# Sheet6.net
KiCad netlist of a schematic drawn in Altium Designer
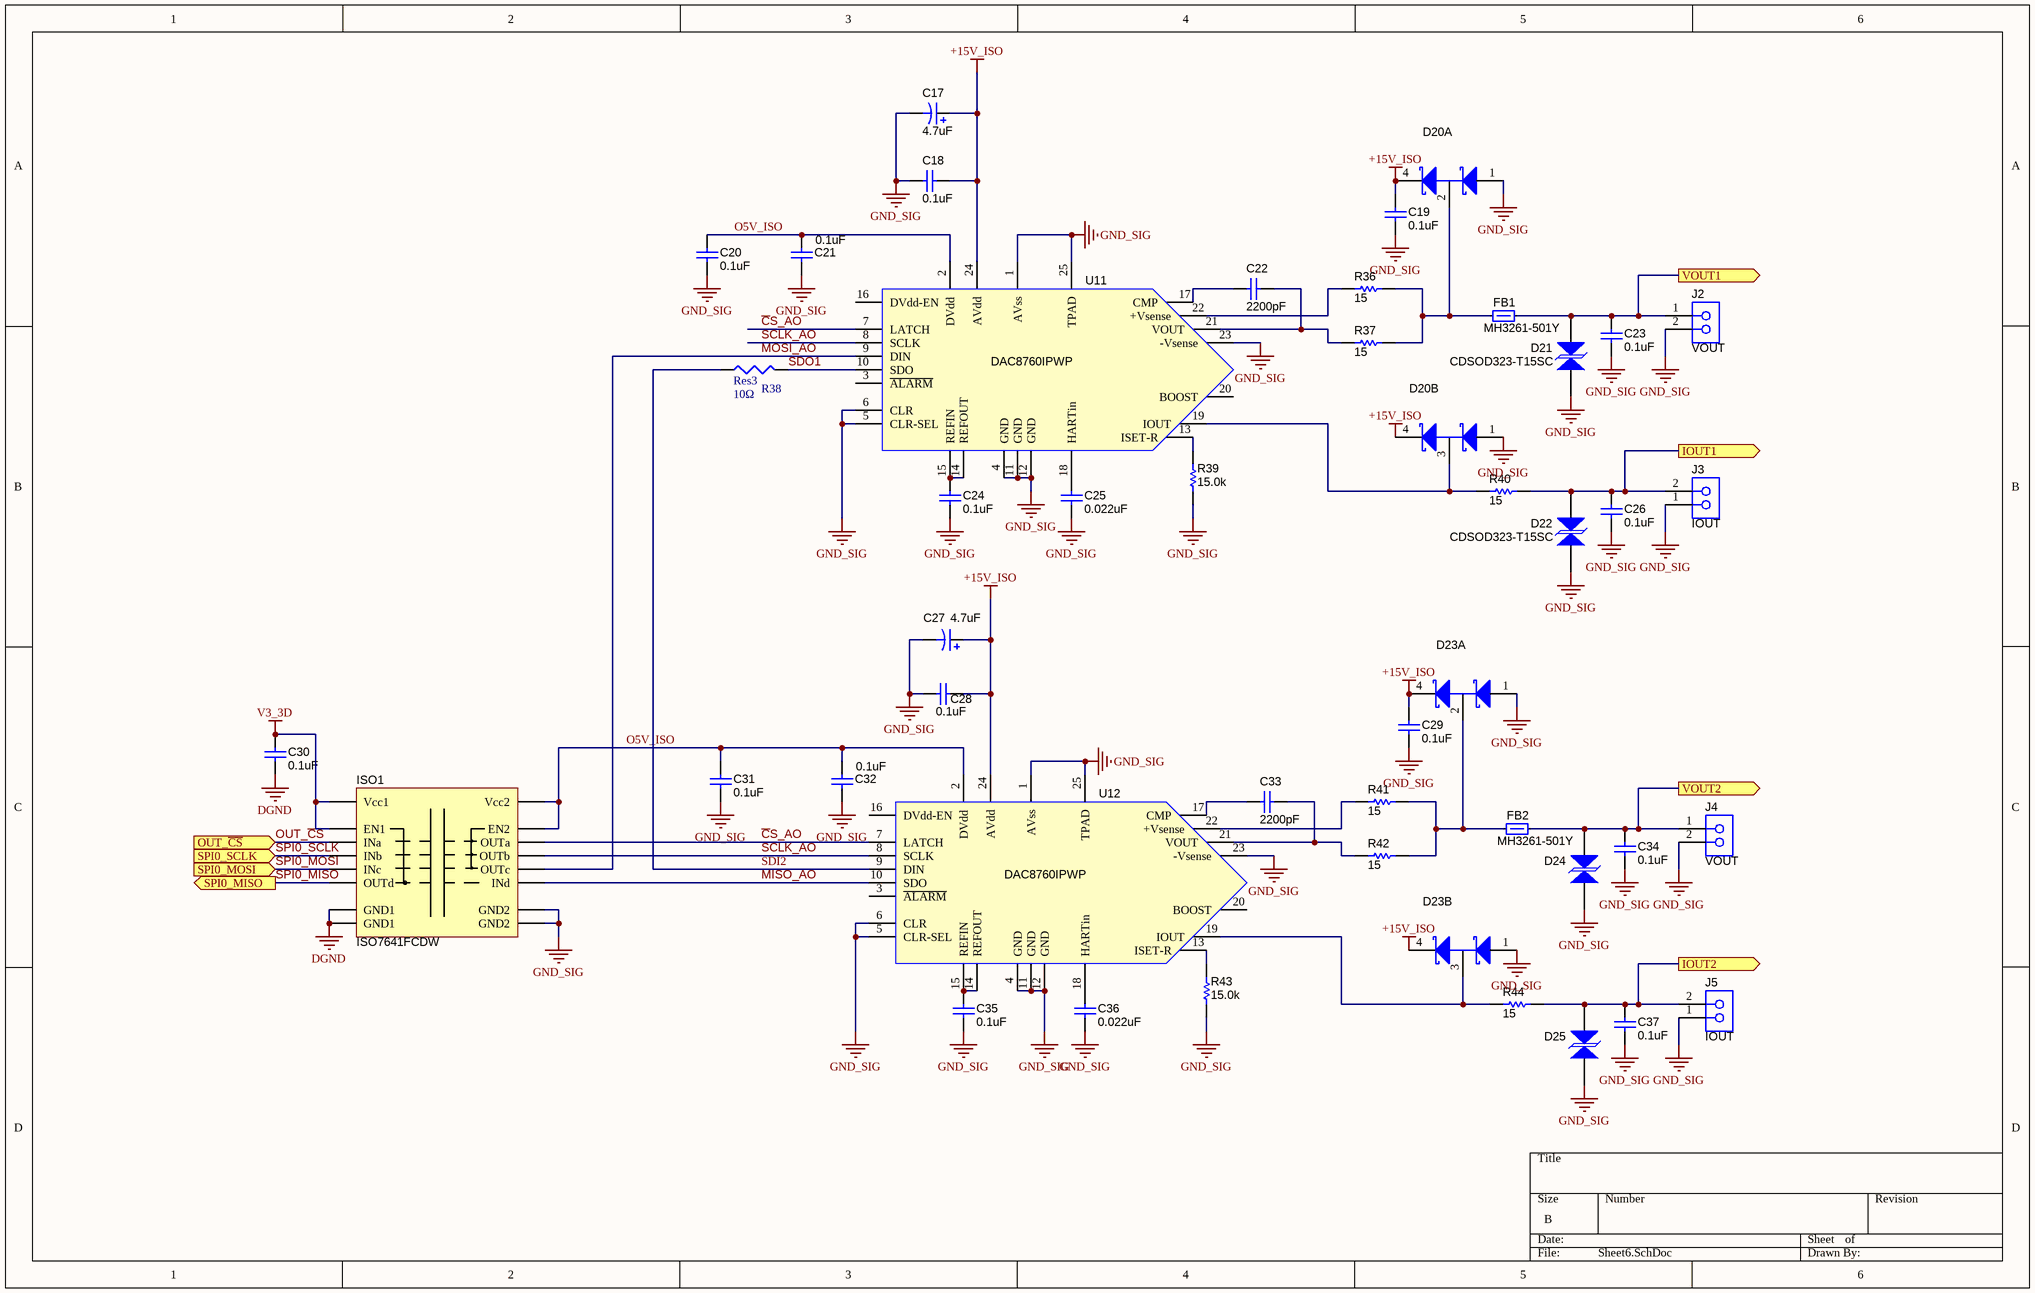
[diagram p0: Sheet6.SchDoc]

(export (version "E")
  (design (tool "Eeschema 10.0.6"))
  (components
    (comp (ref "C17")
      (value "293D475X9035C2TE3")
      (footprint "6032-28")
      (description "CAP, TA, 4.7uF, 35V, +/-10%, 1.9 ohm, SMD")
      (fields
        (field (name "VALUEDISPLAYED") "4.7uF")
        (field (name "MANUFACTURER") "Vishay-Sprague")
        (field (name "PUBLISHER") "Texas Instruments")
      )
      (libsource (lib "Capacitor_Tantalum") (part "293D475X9035C2TE3"))
    )
    (comp (ref "C18")
      (value "GRM188R71H104KA93D")
      (footprint "0805_cap")
      (description "CAP, CERM, 0.1uF, 50V, +/-10%, X7R, 0603")
      (fields
        (field (name "VALUEDISPLAYED") "0.1uF")
        (field (name "MANUFACTURER") "MuRata")
        (field (name "PUBLISHER") "Texas Instruments")
      )
      (libsource (lib "Capacitor_Ceramic") (part "GRM188R71H104KA93D"))
    )
    (comp (ref "C19")
      (value "GRM188R71H104KA93D")
      (footprint "0805_cap")
      (description "CAP, CERM, 0.1uF, 50V, +/-10%, X7R, 0603")
      (fields
        (field (name "VALUEDISPLAYED") "0.1uF")
        (field (name "MANUFACTURER") "MuRata")
        (field (name "PUBLISHER") "Texas Instruments")
      )
      (libsource (lib "Capacitor_Ceramic") (part "GRM188R71H104KA93D"))
    )
    (comp (ref "C20")
      (value "GRM188R71H104KA93D")
      (footprint "0805_cap")
      (description "CAP, CERM, 0.1uF, 50V, +/-10%, X7R, 0603")
      (fields
        (field (name "VALUEDISPLAYED") "0.1uF")
        (field (name "MANUFACTURER") "MuRata")
        (field (name "PUBLISHER") "Texas Instruments")
      )
      (libsource (lib "Capacitor_Ceramic") (part "GRM188R71H104KA93D"))
    )
    (comp (ref "C21")
      (value "GRM188R71H104KA93D")
      (footprint "0805_cap")
      (description "CAP, CERM, 0.1uF, 50V, +/-10%, X7R, 0603")
      (fields
        (field (name "VALUEDISPLAYED") "0.1uF")
        (field (name "MANUFACTURER") "MuRata")
        (field (name "PUBLISHER") "Texas Instruments")
      )
      (libsource (lib "Capacitor_Ceramic") (part "GRM188R71H104KA93D"))
    )
    (comp (ref "C22")
      (value "GRM1885C1H222JA01D")
      (footprint "0805_cap")
      (description "CAP, CERM, 2200pF, 50V, +/-5%, C0G/NP0, 0603")
      (fields
        (field (name "VALUEDISPLAYED") "2200pF")
        (field (name "MANUFACTURER") "MuRata")
        (field (name "PUBLISHER") "Texas Instruments")
      )
      (libsource (lib "Capacitor_Ceramic") (part "GRM1885C1H222JA01D"))
    )
    (comp (ref "C23")
      (value "06035C104KAT2A")
      (footprint "0805_cap")
      (description "CAP, CERM, 0.1uF, 50V, +/-10%, X7R, 0603")
      (fields
        (field (name "VALUEDISPLAYED") "0.1uF")
        (field (name "MANUFACTURER") "AVX")
        (field (name "PUBLISHER") "Texas Instruments")
      )
      (libsource (lib "Capacitor_Ceramic") (part "06035C104KAT2A"))
    )
    (comp (ref "C24")
      (value "06035C104KAT2A")
      (footprint "0805_cap")
      (description "CAP, CERM, 0.1uF, 50V, +/-10%, X7R, 0603")
      (fields
        (field (name "VALUEDISPLAYED") "0.1uF")
        (field (name "MANUFACTURER") "AVX")
        (field (name "PUBLISHER") "Texas Instruments")
      )
      (libsource (lib "Capacitor_Ceramic") (part "06035C104KAT2A"))
    )
    (comp (ref "C25")
      (value "C1608X7R1H223K")
      (footprint "0805_cap")
      (description "CAP, CERM, 0.022uF, 50V, +/-10%, X7R, 0603")
      (fields
        (field (name "VALUEDISPLAYED") "0.022uF")
        (field (name "MANUFACTURER") "TDK")
        (field (name "PUBLISHER") "Texas Instruments")
      )
      (libsource (lib "Capacitor_Ceramic") (part "C1608X7R1H223K"))
    )
    (comp (ref "C26")
      (value "06035C104KAT2A")
      (footprint "0805_cap")
      (description "CAP, CERM, 0.1uF, 50V, +/-10%, X7R, 0603")
      (fields
        (field (name "VALUEDISPLAYED") "0.1uF")
        (field (name "MANUFACTURER") "AVX")
        (field (name "PUBLISHER") "Texas Instruments")
      )
      (libsource (lib "Capacitor_Ceramic") (part "06035C104KAT2A"))
    )
    (comp (ref "C27")
      (value "293D475X9035C2TE3")
      (footprint "6032-28")
      (description "CAP, TA, 4.7uF, 35V, +/-10%, 1.9 ohm, SMD")
      (fields
        (field (name "VALUEDISPLAYED") "4.7uF")
        (field (name "MANUFACTURER") "Vishay-Sprague")
        (field (name "PUBLISHER") "Texas Instruments")
      )
      (libsource (lib "Capacitor_Tantalum") (part "293D475X9035C2TE3"))
    )
    (comp (ref "C28")
      (value "GRM188R71H104KA93D")
      (footprint "0805_cap")
      (description "CAP, CERM, 0.1uF, 50V, +/-10%, X7R, 0603")
      (fields
        (field (name "VALUEDISPLAYED") "0.1uF")
        (field (name "MANUFACTURER") "MuRata")
        (field (name "PUBLISHER") "Texas Instruments")
      )
      (libsource (lib "Capacitor_Ceramic") (part "GRM188R71H104KA93D"))
    )
    (comp (ref "C29")
      (value "GRM188R71H104KA93D")
      (footprint "0805_cap")
      (description "CAP, CERM, 0.1uF, 50V, +/-10%, X7R, 0603")
      (fields
        (field (name "VALUEDISPLAYED") "0.1uF")
        (field (name "MANUFACTURER") "MuRata")
        (field (name "PUBLISHER") "Texas Instruments")
      )
      (libsource (lib "Capacitor_Ceramic") (part "GRM188R71H104KA93D"))
    )
    (comp (ref "C30")
      (value "GRM188R71H104KA93D")
      (footprint "0805_cap")
      (description "CAP, CERM, 0.1uF, 50V, +/-10%, X7R, 0603")
      (fields
        (field (name "VALUEDISPLAYED") "0.1uF")
        (field (name "MANUFACTURER") "MuRata")
        (field (name "PUBLISHER") "Texas Instruments")
      )
      (libsource (lib "Capacitor_Ceramic") (part "GRM188R71H104KA93D"))
    )
    (comp (ref "C31")
      (value "GRM188R71H104KA93D")
      (footprint "0805_cap")
      (description "CAP, CERM, 0.1uF, 50V, +/-10%, X7R, 0603")
      (fields
        (field (name "VALUEDISPLAYED") "0.1uF")
        (field (name "MANUFACTURER") "MuRata")
        (field (name "PUBLISHER") "Texas Instruments")
      )
      (libsource (lib "Capacitor_Ceramic") (part "GRM188R71H104KA93D"))
    )
    (comp (ref "C32")
      (value "GRM188R71H104KA93D")
      (footprint "0805_cap")
      (description "CAP, CERM, 0.1uF, 50V, +/-10%, X7R, 0603")
      (fields
        (field (name "VALUEDISPLAYED") "0.1uF")
        (field (name "MANUFACTURER") "MuRata")
        (field (name "PUBLISHER") "Texas Instruments")
      )
      (libsource (lib "Capacitor_Ceramic") (part "GRM188R71H104KA93D"))
    )
    (comp (ref "C33")
      (value "GRM1885C1H222JA01D")
      (footprint "0805_cap")
      (description "CAP, CERM, 2200pF, 50V, +/-5%, C0G/NP0, 0603")
      (fields
        (field (name "VALUEDISPLAYED") "2200pF")
        (field (name "MANUFACTURER") "MuRata")
        (field (name "PUBLISHER") "Texas Instruments")
      )
      (libsource (lib "Capacitor_Ceramic") (part "GRM1885C1H222JA01D"))
    )
    (comp (ref "C34")
      (value "06035C104KAT2A")
      (footprint "0805_cap")
      (description "CAP, CERM, 0.1uF, 50V, +/-10%, X7R, 0603")
      (fields
        (field (name "VALUEDISPLAYED") "0.1uF")
        (field (name "MANUFACTURER") "AVX")
        (field (name "PUBLISHER") "Texas Instruments")
      )
      (libsource (lib "Capacitor_Ceramic") (part "06035C104KAT2A"))
    )
    (comp (ref "C35")
      (value "06035C104KAT2A")
      (footprint "0805_cap")
      (description "CAP, CERM, 0.1uF, 50V, +/-10%, X7R, 0603")
      (fields
        (field (name "VALUEDISPLAYED") "0.1uF")
        (field (name "MANUFACTURER") "AVX")
        (field (name "PUBLISHER") "Texas Instruments")
      )
      (libsource (lib "Capacitor_Ceramic") (part "06035C104KAT2A"))
    )
    (comp (ref "C36")
      (value "C1608X7R1H223K")
      (footprint "0805_cap")
      (description "CAP, CERM, 0.022uF, 50V, +/-10%, X7R, 0603")
      (fields
        (field (name "VALUEDISPLAYED") "0.022uF")
        (field (name "MANUFACTURER") "TDK")
        (field (name "PUBLISHER") "Texas Instruments")
      )
      (libsource (lib "Capacitor_Ceramic") (part "C1608X7R1H223K"))
    )
    (comp (ref "C37")
      (value "06035C104KAT2A")
      (footprint "0805_cap")
      (description "CAP, CERM, 0.1uF, 50V, +/-10%, X7R, 0603")
      (fields
        (field (name "VALUEDISPLAYED") "0.1uF")
        (field (name "MANUFACTURER") "AVX")
        (field (name "PUBLISHER") "Texas Instruments")
      )
      (libsource (lib "Capacitor_Ceramic") (part "06035C104KAT2A"))
    )
    (comp (ref "D20")
      (value "~")
      (footprint "SOT-143")
      (description "IC TVS ARRAY 2-LINE 70V SOT-143")
      (fields
        (field (name "MANUFACTURER") "Bourns")
        (field (name "PARTNUMBER") "CD143A-SR70")
        (field (name "SYMBOLCREATOR") "Use LDAP id")
      )
      (libsource (lib "DAC8760-Symbols") (part "CD143A-SR70"))
    )
    (comp (ref "D21")
      (value "CDSOD323-T15SC")
      (footprint "sod-323")
      (description "DIODE TVS ARRAY 15V SOD323")
      (fields (field (name "MANUFACTURER") "Bourns") (field (name "SYMBOLCREATOR") "Use LDAP id"))
      (libsource (lib "DAC8760-Symbols") (part "SMAJ15CA"))
    )
    (comp (ref "D22")
      (value "CDSOD323-T15SC")
      (footprint "sod-323")
      (description "DIODE TVS ARRAY 15V SOD323")
      (fields (field (name "MANUFACTURER") "Bourns") (field (name "SYMBOLCREATOR") "Use LDAP id"))
      (libsource (lib "DAC8760-Symbols") (part "SMAJ15CA"))
    )
    (comp (ref "D23")
      (value "~")
      (footprint "SOT-143")
      (description "IC TVS ARRAY 2-LINE 70V SOT-143")
      (fields
        (field (name "MANUFACTURER") "Bourns")
        (field (name "PARTNUMBER") "CD143A-SR70")
        (field (name "SYMBOLCREATOR") "Use LDAP id")
      )
      (libsource (lib "DAC8760-Symbols") (part "CD143A-SR70"))
    )
    (comp (ref "D24")
      (value "~")
      (footprint "sod-323")
      (description "DIODE TVS ARRAY 15V SOD323")
      (fields
        (field (name "MANUFACTURER") "Bourns")
        (field (name "PARTNUMBER") "CDSOD323-T15SC")
        (field (name "SYMBOLCREATOR") "Use LDAP id")
      )
      (libsource (lib "DAC8760-Symbols") (part "SMAJ15CA"))
    )
    (comp (ref "D25")
      (value "~")
      (footprint "sod-323")
      (description "DIODE TVS ARRAY 15V SOD323")
      (fields
        (field (name "MANUFACTURER") "Bourns")
        (field (name "PARTNUMBER") "CDSOD323-T15SC")
        (field (name "SYMBOLCREATOR") "Use LDAP id")
      )
      (libsource (lib "DAC8760-Symbols") (part "SMAJ15CA"))
    )
    (comp (ref "FB1")
      (value "MH3261-501Y")
      (footprint "1210")
      (description "BEAD FERRITE 500 OHM 3.0A 3216")
      (fields (field (name "MANUFACTURER") "Bourns Inc.") (field (name "PUBLISHER") "Texas Instruments"))
      (libsource (lib "MiscParts") (part "Ferrite_Bead"))
    )
    (comp (ref "FB2")
      (value "MH3261-501Y")
      (footprint "1210")
      (description "BEAD FERRITE 500 OHM 3.0A 3216")
      (fields (field (name "MANUFACTURER") "Bourns Inc.") (field (name "PUBLISHER") "Texas Instruments"))
      (libsource (lib "MiscParts") (part "Ferrite_Bead"))
    )
    (comp (ref "ISO1")
      (value "ISO7641FCDW")
      (footprint "M16B_N")
      (description "ISOLATOR DGTL 25MBPS 4CH 16SOIC")
      (fields
        (field (name "MANUFACTURER") "Texas Instruments Inc")
        (field (name "SYMBOLCREATOR") "Use LDAP id")
      )
      (libsource (lib "DAC8760-Symbols") (part "ISO7241"))
    )
    (comp (ref "J2")
      (value "VOUT")
      (footprint "ED555/2DS")
      (description "TERMINAL BLOCK 3.5MM 2POS PCB")
      (fields
        (field (name "PARTNUMBER") "ED555/2DS")
        (field (name "MANUFACTURER") "On Shore Technology Inc")
        (field (name "PUBLISHER") "Texas Instruments")
      )
      (libsource (lib "") (part "1727010_1"))
    )
    (comp (ref "J3")
      (value "IOUT")
      (footprint "ED555/2DS")
      (description "TERMINAL BLOCK 3.5MM 2POS PCB")
      (fields
        (field (name "PARTNUMBER") "ED555/2DS")
        (field (name "MANUFACTURER") "On Shore Technology Inc")
        (field (name "PUBLISHER") "Texas Instruments")
      )
      (libsource (lib "Connectors") (part "1727010"))
    )
    (comp (ref "J4")
      (value "VOUT")
      (footprint "ED555/2DS")
      (description "TERMINAL BLOCK 3.5MM 2POS PCB")
      (fields
        (field (name "PARTNUMBER") "ED555/2DS")
        (field (name "MANUFACTURER") "On Shore Technology Inc")
        (field (name "PUBLISHER") "Texas Instruments")
      )
      (libsource (lib "") (part "1727010_1"))
    )
    (comp (ref "J5")
      (value "IOUT")
      (footprint "ED555/2DS")
      (description "TERMINAL BLOCK 3.5MM 2POS PCB")
      (fields
        (field (name "PARTNUMBER") "ED555/2DS")
        (field (name "MANUFACTURER") "On Shore Technology Inc")
        (field (name "PUBLISHER") "Texas Instruments")
      )
      (libsource (lib "Connectors") (part "1727010"))
    )
    (comp (ref "R36")
      (value "15")
      (footprint "0805")
      (description "RES, 15 ohm, 5%, 0.1W, 0603")
      (fields
        (field (name "PARTNUMBER") "CRCW060315R0JNEA")
        (field (name "MANUFACTURER") "Vishay-Dale")
        (field (name "PUBLISHER") "Texas Instruments")
      )
      (libsource (lib "Resistor_0603") (part "CRCW060315R0JNEA"))
    )
    (comp (ref "R37")
      (value "15")
      (footprint "0805")
      (description "RES, 15 ohm, 5%, 0.1W, 0603")
      (fields
        (field (name "PARTNUMBER") "CRCW060315R0JNEA")
        (field (name "MANUFACTURER") "Vishay-Dale")
        (field (name "PUBLISHER") "Texas Instruments")
      )
      (libsource (lib "Resistor_0603") (part "CRCW060315R0JNEA"))
    )
    (comp (ref "R38")
      (value "Res3")
      (footprint "0805")
      (description "Resistor")
      (fields (field (name "ALTIUM_VALUE") "10Ω") (field (name "PUBLISHER") "Altium Limited"))
      (libsource (lib "Miscellaneous Devices") (part "Res3"))
    )
    (comp (ref "R39")
      (value "15.0k")
      (footprint "0805")
      (description "RES, 15.0k ohm, 0.1%, 0.1W, 0603")
      (fields
        (field (name "PARTNUMBER") "RT0603BRD0715KL")
        (field (name "MANUFACTURER") "Yageo America")
        (field (name "PUBLISHER") "Texas Instruments")
      )
      (libsource (lib "Resistor_0603") (part "RT0603BRD0715KL"))
    )
    (comp (ref "R40")
      (value "15")
      (footprint "1210")
      (description "RES 15 OHM 1W 5% 2512")
      (fields
        (field (name "PARTNUMBER") "RPC2512JT15R0")
        (field (name "MANUFACTURER") "Stackpole Electronics")
      )
      (libsource (lib "Resistor_OtherSMT") (part "CRA2512-FZ-R080ELF"))
    )
    (comp (ref "R41")
      (value "15")
      (footprint "0805")
      (description "RES, 15 ohm, 5%, 0.1W, 0603")
      (fields
        (field (name "PARTNUMBER") "CRCW060315R0JNEA")
        (field (name "MANUFACTURER") "Vishay-Dale")
        (field (name "PUBLISHER") "Texas Instruments")
      )
      (libsource (lib "Resistor_0603") (part "CRCW060315R0JNEA"))
    )
    (comp (ref "R42")
      (value "15")
      (footprint "0805")
      (description "RES, 15 ohm, 5%, 0.1W, 0603")
      (fields
        (field (name "PARTNUMBER") "CRCW060315R0JNEA")
        (field (name "MANUFACTURER") "Vishay-Dale")
        (field (name "PUBLISHER") "Texas Instruments")
      )
      (libsource (lib "Resistor_0603") (part "CRCW060315R0JNEA"))
    )
    (comp (ref "R43")
      (value "15.0k")
      (footprint "0805")
      (description "RES, 15.0k ohm, 0.1%, 0.1W, 0603")
      (fields
        (field (name "PARTNUMBER") "RT0603BRD0715KL")
        (field (name "MANUFACTURER") "Yageo America")
        (field (name "PUBLISHER") "Texas Instruments")
      )
      (libsource (lib "Resistor_0603") (part "RT0603BRD0715KL"))
    )
    (comp (ref "R44")
      (value "15")
      (footprint "1210")
      (description "RES 15 OHM 1W 5% 2512")
      (fields
        (field (name "PARTNUMBER") "RPC2512JT15R0")
        (field (name "MANUFACTURER") "Stackpole Electronics")
      )
      (libsource (lib "Resistor_OtherSMT") (part "CRA2512-FZ-R080ELF"))
    )
    (comp (ref "U11")
      (value "DAC8760IPWP")
      (footprint "PWP24-DIE84X166")
      (description "1-Channel, 16-Bit, Programmable Current/Voltage Output DAC for 4-20mA Current Loop Applications")
      (fields
        (field (name "MANUFACTURER") "Texas Instruments")
        (field (name "SYMBOLCREATOR") "x0120606")
        (field (name "PUBLISHER") "Texas Instruments")
      )
      (libsource (lib "dolphi_ecs") (part "DAC8760IPWP_1"))
    )
    (comp (ref "U12")
      (value "DAC8760IPWP")
      (footprint "PWP24-DIE84X166")
      (description "1-Channel, 16-Bit, Programmable Current/Voltage Output DAC for 4-20mA Current Loop Applications")
      (fields
        (field (name "MANUFACTURER") "Texas Instruments")
        (field (name "SYMBOLCREATOR") "x0120606")
        (field (name "PUBLISHER") "Texas Instruments")
      )
      (libsource (lib "dolphi_ecs") (part "DAC8760IPWP_1"))
    )
  )
  (nets
    (net (code "1") (name "+15V_ISO") (class "Default")
      (node (ref "C17") (pin "1") (pinfunction "+_1") (pintype "passive"))
      (node (ref "C18") (pin "1") (pinfunction "1_1") (pintype "passive"))
      (node (ref "C19") (pin "1") (pinfunction "1_1") (pintype "passive"))
      (node (ref "C27") (pin "1") (pinfunction "+_1") (pintype "passive"))
      (node (ref "C28") (pin "1") (pinfunction "1_1") (pintype "passive"))
      (node (ref "C29") (pin "1") (pinfunction "1_1") (pintype "passive"))
      (node (ref "D20") (pin "4") (pinfunction "4_4") (pintype "passive"))
      (node (ref "D23") (pin "4") (pinfunction "4_4") (pintype "passive"))
      (node (ref "U11") (pin "24") (pinfunction "AVdd_24") (pintype "passive"))
      (node (ref "U12") (pin "24") (pinfunction "AVdd_24") (pintype "passive"))
    )
    (net (code "2") (name "/IOUT1") (class "Default")
      (node (ref "C26") (pin "1") (pinfunction "1_1") (pintype "passive"))
      (node (ref "D22") (pin "1") (pinfunction "1_1") (pintype "passive"))
      (node (ref "J3") (pin "2") (pinfunction "2_2") (pintype "passive"))
      (node (ref "R40") (pin "2") (pinfunction "2_2") (pintype "passive"))
    )
    (net (code "3") (name "/IOUT2") (class "Default")
      (node (ref "C37") (pin "1") (pinfunction "1_1") (pintype "passive"))
      (node (ref "D25") (pin "1") (pinfunction "1_1") (pintype "passive"))
      (node (ref "J5") (pin "2") (pinfunction "2_2") (pintype "passive"))
      (node (ref "R44") (pin "2") (pinfunction "2_2") (pintype "passive"))
    )
    (net (code "4") (name "/MISO_AO") (class "Default")
      (node (ref "ISO1") (pin "11") (pinfunction "INd_11") (pintype "passive"))
      (node (ref "U12") (pin "10") (pinfunction "SDO_10") (pintype "passive"))
    )
    (net (code "5") (name "/MOSI_AO") (class "Default")
      (node (ref "ISO1") (pin "12") (pinfunction "OUTc_12") (pintype "passive"))
      (node (ref "U11") (pin "9") (pinfunction "DIN_9") (pintype "passive"))
    )
    (net (code "6") (name "/O5V_ISO") (class "Default")
      (node (ref "C20") (pin "1") (pinfunction "1_1") (pintype "passive"))
      (node (ref "C21") (pin "1") (pinfunction "1_1") (pintype "passive"))
      (node (ref "C31") (pin "1") (pinfunction "1_1") (pintype "passive"))
      (node (ref "C32") (pin "1") (pinfunction "1_1") (pintype "passive"))
      (node (ref "ISO1") (pin "10") (pinfunction "EN2_10") (pintype "passive"))
      (node (ref "ISO1") (pin "16") (pinfunction "Vcc2_16") (pintype "passive"))
      (node (ref "U11") (pin "2") (pinfunction "DVdd_2") (pintype "passive"))
      (node (ref "U12") (pin "2") (pinfunction "DVdd_2") (pintype "passive"))
    )
    (net (code "7") (name "/OUT_~{CS}") (class "Default")
      (node (ref "ISO1") (pin "3") (pinfunction "INa_3") (pintype "passive"))
    )
    (net (code "8") (name "/SCLK_AO") (class "Default")
      (node (ref "ISO1") (pin "13") (pinfunction "OUTb_13") (pintype "passive"))
      (node (ref "U11") (pin "8") (pinfunction "SCLK_8") (pintype "passive"))
      (node (ref "U12") (pin "8") (pinfunction "SCLK_8") (pintype "passive"))
    )
    (net (code "9") (name "/SDI2") (class "Default")
      (node (ref "R38") (pin "1") (pinfunction "1_1") (pintype "passive"))
      (node (ref "U12") (pin "9") (pinfunction "DIN_9") (pintype "passive"))
    )
    (net (code "10") (name "/SDO1") (class "Default")
      (node (ref "R38") (pin "2") (pinfunction "2_2") (pintype "passive"))
      (node (ref "U11") (pin "10") (pinfunction "SDO_10") (pintype "passive"))
    )
    (net (code "11") (name "/SPI0_MISO") (class "Default")
      (node (ref "ISO1") (pin "6") (pinfunction "OUTd_6") (pintype "passive"))
    )
    (net (code "12") (name "/SPI0_MOSI") (class "Default")
      (node (ref "ISO1") (pin "5") (pinfunction "INc_5") (pintype "passive"))
    )
    (net (code "13") (name "/SPI0_SCLK") (class "Default")
      (node (ref "ISO1") (pin "4") (pinfunction "INb_4") (pintype "passive"))
    )
    (net (code "14") (name "/VOUT1") (class "Default")
      (node (ref "C23") (pin "1") (pinfunction "1_1") (pintype "passive"))
      (node (ref "D21") (pin "1") (pinfunction "1_1") (pintype "passive"))
      (node (ref "FB1") (pin "2") (pinfunction "2_2") (pintype "passive"))
      (node (ref "J2") (pin "1") (pinfunction "1_1") (pintype "passive"))
    )
    (net (code "15") (name "/VOUT2") (class "Default")
      (node (ref "C34") (pin "1") (pinfunction "1_1") (pintype "passive"))
      (node (ref "D24") (pin "1") (pinfunction "1_1") (pintype "passive"))
      (node (ref "FB2") (pin "2") (pinfunction "2_2") (pintype "passive"))
      (node (ref "J4") (pin "1") (pinfunction "1_1") (pintype "passive"))
    )
    (net (code "16") (name "/~{C}S_AO") (class "Default")
      (node (ref "ISO1") (pin "14") (pinfunction "OUTa_14") (pintype "passive"))
      (node (ref "U11") (pin "7") (pinfunction "LATCH_7") (pintype "passive"))
      (node (ref "U12") (pin "7") (pinfunction "LATCH_7") (pintype "passive"))
    )
    (net (code "17") (name "DGND") (class "Default")
      (node (ref "C30") (pin "2") (pinfunction "2_2") (pintype "passive"))
      (node (ref "ISO1") (pin "2") (pinfunction "GND1_2") (pintype "passive"))
      (node (ref "ISO1") (pin "8") (pinfunction "GND1_8") (pintype "passive"))
    )
    (net (code "18") (name "GND_SIG") (class "Default")
      (node (ref "C17") (pin "2") (pinfunction "-_2") (pintype "passive"))
      (node (ref "C18") (pin "2") (pinfunction "2_2") (pintype "passive"))
      (node (ref "C19") (pin "2") (pinfunction "2_2") (pintype "passive"))
      (node (ref "C20") (pin "2") (pinfunction "2_2") (pintype "passive"))
      (node (ref "C21") (pin "2") (pinfunction "2_2") (pintype "passive"))
      (node (ref "C23") (pin "2") (pinfunction "2_2") (pintype "passive"))
      (node (ref "C24") (pin "2") (pinfunction "2_2") (pintype "passive"))
      (node (ref "C25") (pin "2") (pinfunction "2_2") (pintype "passive"))
      (node (ref "C26") (pin "2") (pinfunction "2_2") (pintype "passive"))
      (node (ref "C27") (pin "2") (pinfunction "-_2") (pintype "passive"))
      (node (ref "C28") (pin "2") (pinfunction "2_2") (pintype "passive"))
      (node (ref "C29") (pin "2") (pinfunction "2_2") (pintype "passive"))
      (node (ref "C31") (pin "2") (pinfunction "2_2") (pintype "passive"))
      (node (ref "C32") (pin "2") (pinfunction "2_2") (pintype "passive"))
      (node (ref "C34") (pin "2") (pinfunction "2_2") (pintype "passive"))
      (node (ref "C35") (pin "2") (pinfunction "2_2") (pintype "passive"))
      (node (ref "C36") (pin "2") (pinfunction "2_2") (pintype "passive"))
      (node (ref "C37") (pin "2") (pinfunction "2_2") (pintype "passive"))
      (node (ref "D20") (pin "1") (pinfunction "1_1") (pintype "passive"))
      (node (ref "D21") (pin "2") (pinfunction "2_2") (pintype "passive"))
      (node (ref "D22") (pin "2") (pinfunction "2_2") (pintype "passive"))
      (node (ref "D23") (pin "1") (pinfunction "1_1") (pintype "passive"))
      (node (ref "D24") (pin "2") (pinfunction "2_2") (pintype "passive"))
      (node (ref "D25") (pin "2") (pinfunction "2_2") (pintype "passive"))
      (node (ref "ISO1") (pin "15") (pinfunction "GND2_15") (pintype "passive"))
      (node (ref "ISO1") (pin "9") (pinfunction "GND2_9") (pintype "passive"))
      (node (ref "J2") (pin "2") (pinfunction "2_2") (pintype "passive"))
      (node (ref "J3") (pin "1") (pinfunction "1_1") (pintype "passive"))
      (node (ref "J4") (pin "2") (pinfunction "2_2") (pintype "passive"))
      (node (ref "J5") (pin "1") (pinfunction "1_1") (pintype "passive"))
      (node (ref "R39") (pin "1") (pinfunction "1_1") (pintype "passive"))
      (node (ref "R43") (pin "1") (pinfunction "1_1") (pintype "passive"))
      (node (ref "U11") (pin "1") (pinfunction "AVss_1") (pintype "passive"))
      (node (ref "U11") (pin "11") (pinfunction "GND_11") (pintype "passive"))
      (node (ref "U11") (pin "12") (pinfunction "GND_12") (pintype "passive"))
      (node (ref "U11") (pin "23") (pinfunction "-Vsense_23") (pintype "passive"))
      (node (ref "U11") (pin "25") (pinfunction "TPAD_25") (pintype "passive"))
      (node (ref "U11") (pin "4") (pinfunction "GND_4") (pintype "passive"))
      (node (ref "U11") (pin "5") (pinfunction "CLR-SEL_5") (pintype "passive"))
      (node (ref "U11") (pin "6") (pinfunction "CLR_6") (pintype "passive"))
      (node (ref "U12") (pin "1") (pinfunction "AVss_1") (pintype "passive"))
      (node (ref "U12") (pin "11") (pinfunction "GND_11") (pintype "passive"))
      (node (ref "U12") (pin "12") (pinfunction "GND_12") (pintype "passive"))
      (node (ref "U12") (pin "23") (pinfunction "-Vsense_23") (pintype "passive"))
      (node (ref "U12") (pin "25") (pinfunction "TPAD_25") (pintype "passive"))
      (node (ref "U12") (pin "4") (pinfunction "GND_4") (pintype "passive"))
      (node (ref "U12") (pin "5") (pinfunction "CLR-SEL_5") (pintype "passive"))
      (node (ref "U12") (pin "6") (pinfunction "CLR_6") (pintype "passive"))
    )
    (net (code "19") (name "Net-(D20-Pad2)") (class "Default")
      (node (ref "D20") (pin "2") (pinfunction "2_2") (pintype "passive"))
      (node (ref "FB1") (pin "1") (pinfunction "1_1") (pintype "passive"))
      (node (ref "R36") (pin "2") (pinfunction "2_2") (pintype "passive"))
      (node (ref "R37") (pin "2") (pinfunction "2_2") (pintype "passive"))
    )
    (net (code "20") (name "Net-(D23-Pad2)") (class "Default")
      (node (ref "D23") (pin "2") (pinfunction "2_2") (pintype "passive"))
      (node (ref "FB2") (pin "1") (pinfunction "1_1") (pintype "passive"))
      (node (ref "R41") (pin "2") (pinfunction "2_2") (pintype "passive"))
      (node (ref "R42") (pin "2") (pinfunction "2_2") (pintype "passive"))
    )
    (net (code "21") (name "Net-(U11-+Vsense)") (class "Default")
      (node (ref "R36") (pin "1") (pinfunction "1_1") (pintype "passive"))
      (node (ref "U11") (pin "22") (pinfunction "+Vsense_22") (pintype "passive"))
    )
    (net (code "22") (name "Net-(U11-CMP)") (class "Default")
      (node (ref "C22") (pin "2") (pinfunction "2_2") (pintype "passive"))
      (node (ref "U11") (pin "17") (pinfunction "CMP_17") (pintype "passive"))
    )
    (net (code "23") (name "Net-(U11-HARTin)") (class "Default")
      (node (ref "C25") (pin "1") (pinfunction "1_1") (pintype "passive"))
      (node (ref "U11") (pin "18") (pinfunction "HARTin_18") (pintype "passive"))
    )
    (net (code "24") (name "Net-(U11-IOUT)") (class "Default")
      (node (ref "D20") (pin "3") (pinfunction "3_3") (pintype "passive"))
      (node (ref "R40") (pin "1") (pinfunction "1_1") (pintype "passive"))
      (node (ref "U11") (pin "19") (pinfunction "IOUT_19") (pintype "passive"))
    )
    (net (code "25") (name "Net-(U11-ISET-R)") (class "Default")
      (node (ref "R39") (pin "2") (pinfunction "2_2") (pintype "passive"))
      (node (ref "U11") (pin "13") (pinfunction "ISET-R_13") (pintype "passive"))
    )
    (net (code "26") (name "Net-(U11-REFIN)") (class "Default")
      (node (ref "C24") (pin "1") (pinfunction "1_1") (pintype "passive"))
      (node (ref "U11") (pin "14") (pinfunction "REFOUT_14") (pintype "passive"))
      (node (ref "U11") (pin "15") (pinfunction "REFIN_15") (pintype "passive"))
    )
    (net (code "27") (name "Net-(U11-VOUT)") (class "Default")
      (node (ref "C22") (pin "1") (pinfunction "1_1") (pintype "passive"))
      (node (ref "R37") (pin "1") (pinfunction "1_1") (pintype "passive"))
      (node (ref "U11") (pin "21") (pinfunction "VOUT_21") (pintype "passive"))
    )
    (net (code "28") (name "Net-(U12-+Vsense)") (class "Default")
      (node (ref "R41") (pin "1") (pinfunction "1_1") (pintype "passive"))
      (node (ref "U12") (pin "22") (pinfunction "+Vsense_22") (pintype "passive"))
    )
    (net (code "29") (name "Net-(U12-CMP)") (class "Default")
      (node (ref "C33") (pin "2") (pinfunction "2_2") (pintype "passive"))
      (node (ref "U12") (pin "17") (pinfunction "CMP_17") (pintype "passive"))
    )
    (net (code "30") (name "Net-(U12-HARTin)") (class "Default")
      (node (ref "C36") (pin "1") (pinfunction "1_1") (pintype "passive"))
      (node (ref "U12") (pin "18") (pinfunction "HARTin_18") (pintype "passive"))
    )
    (net (code "31") (name "Net-(U12-IOUT)") (class "Default")
      (node (ref "D23") (pin "3") (pinfunction "3_3") (pintype "passive"))
      (node (ref "R44") (pin "1") (pinfunction "1_1") (pintype "passive"))
      (node (ref "U12") (pin "19") (pinfunction "IOUT_19") (pintype "passive"))
    )
    (net (code "32") (name "Net-(U12-ISET-R)") (class "Default")
      (node (ref "R43") (pin "2") (pinfunction "2_2") (pintype "passive"))
      (node (ref "U12") (pin "13") (pinfunction "ISET-R_13") (pintype "passive"))
    )
    (net (code "33") (name "Net-(U12-REFIN)") (class "Default")
      (node (ref "C35") (pin "1") (pinfunction "1_1") (pintype "passive"))
      (node (ref "U12") (pin "14") (pinfunction "REFOUT_14") (pintype "passive"))
      (node (ref "U12") (pin "15") (pinfunction "REFIN_15") (pintype "passive"))
    )
    (net (code "34") (name "Net-(U12-VOUT)") (class "Default")
      (node (ref "C33") (pin "1") (pinfunction "1_1") (pintype "passive"))
      (node (ref "R42") (pin "1") (pinfunction "1_1") (pintype "passive"))
      (node (ref "U12") (pin "21") (pinfunction "VOUT_21") (pintype "passive"))
    )
    (net (code "35") (name "V3_3D") (class "Default")
      (node (ref "C30") (pin "1") (pinfunction "1_1") (pintype "passive"))
      (node (ref "ISO1") (pin "1") (pinfunction "Vcc1_1") (pintype "passive"))
      (node (ref "ISO1") (pin "7") (pinfunction "EN1_7") (pintype "passive"))
    )
    (net (code "36") (name "unconnected-(U11-BOOST-Pad20)") (class "Default")
      (node (ref "U11") (pin "20") (pinfunction "BOOST_20") (pintype "passive"))
    )
    (net (code "37") (name "unconnected-(U11-DVdd-EN-Pad16)") (class "Default")
      (node (ref "U11") (pin "16") (pinfunction "DVdd-EN_16") (pintype "passive"))
    )
    (net (code "38") (name "unconnected-(U11-~{ALARM}-Pad3)") (class "Default")
      (node (ref "U11") (pin "3") (pinfunction "~{ALARM}_3") (pintype "passive"))
    )
    (net (code "39") (name "unconnected-(U12-BOOST-Pad20)") (class "Default")
      (node (ref "U12") (pin "20") (pinfunction "BOOST_20") (pintype "passive"))
    )
    (net (code "40") (name "unconnected-(U12-DVdd-EN-Pad16)") (class "Default")
      (node (ref "U12") (pin "16") (pinfunction "DVdd-EN_16") (pintype "passive"))
    )
    (net (code "41") (name "unconnected-(U12-~{ALARM}-Pad3)") (class "Default")
      (node (ref "U12") (pin "3") (pinfunction "~{ALARM}_3") (pintype "passive"))
    )
  )
)
